# revA.net
KiCad netlist of a schematic drawn in EAGLE
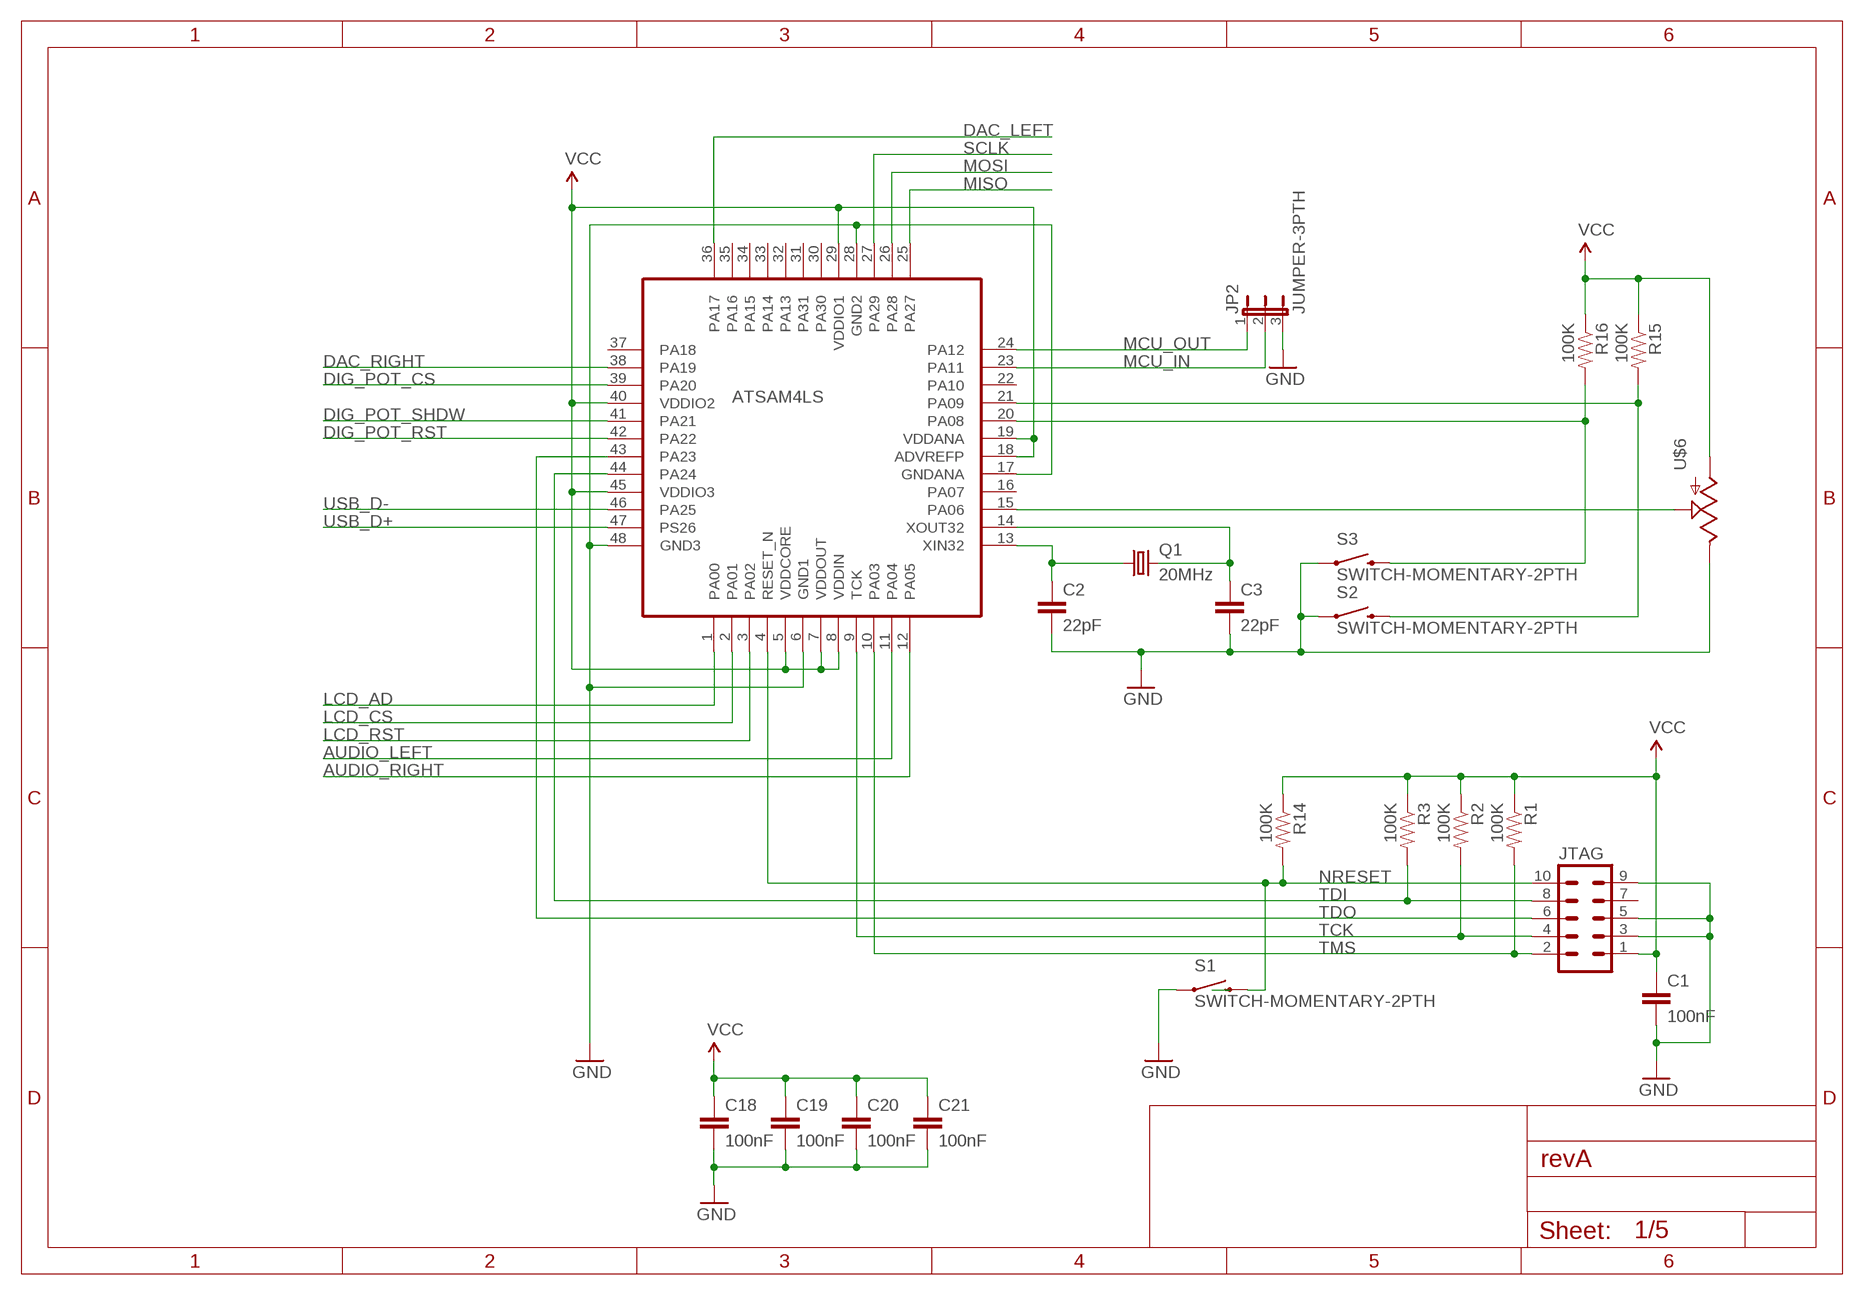
[diagram p0: schematic, sheet 1]
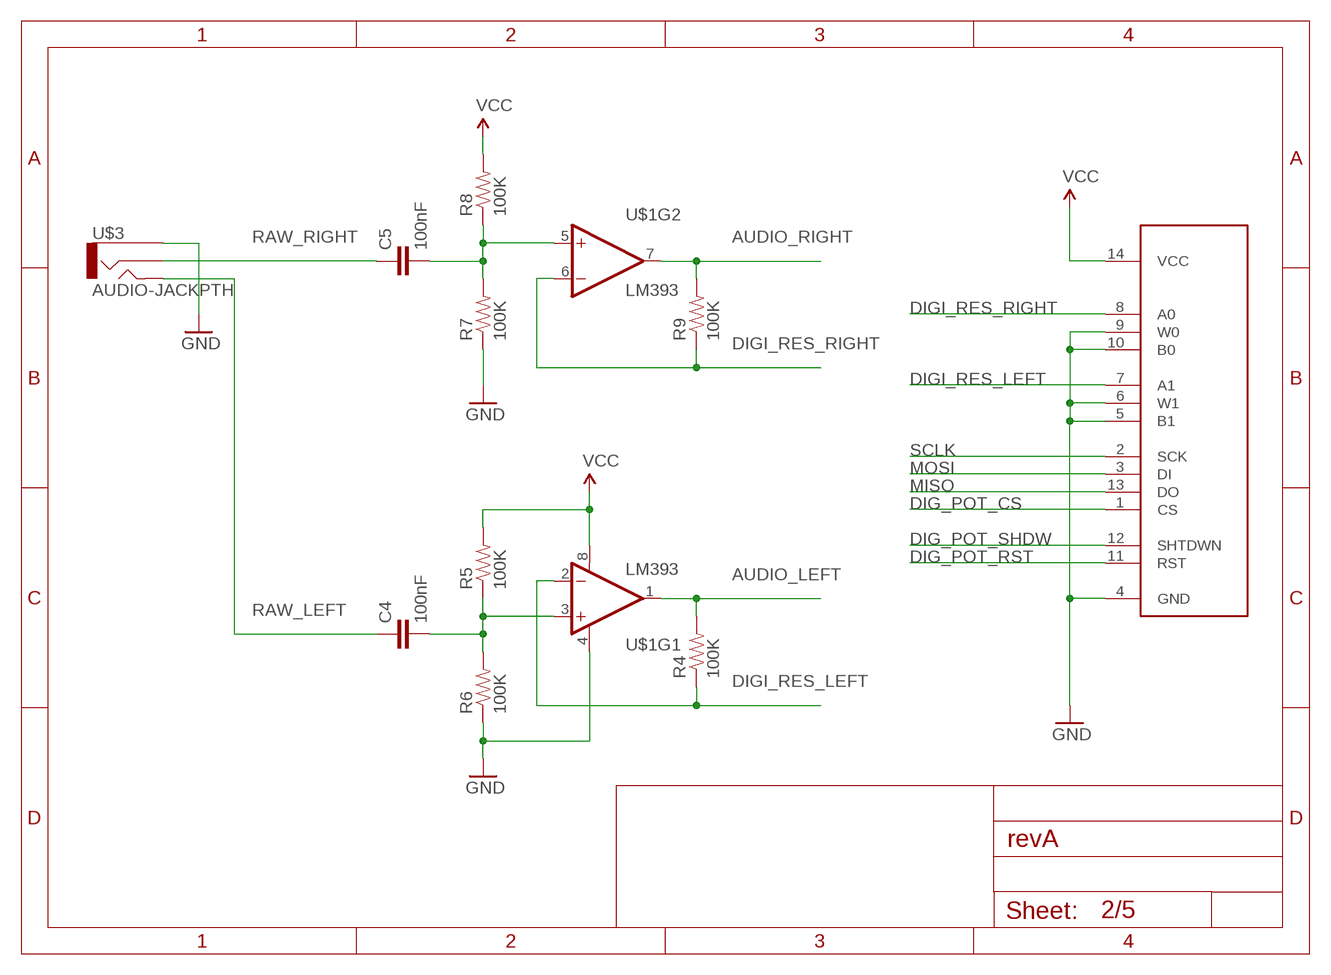
[diagram p1: schematic, sheet 2]
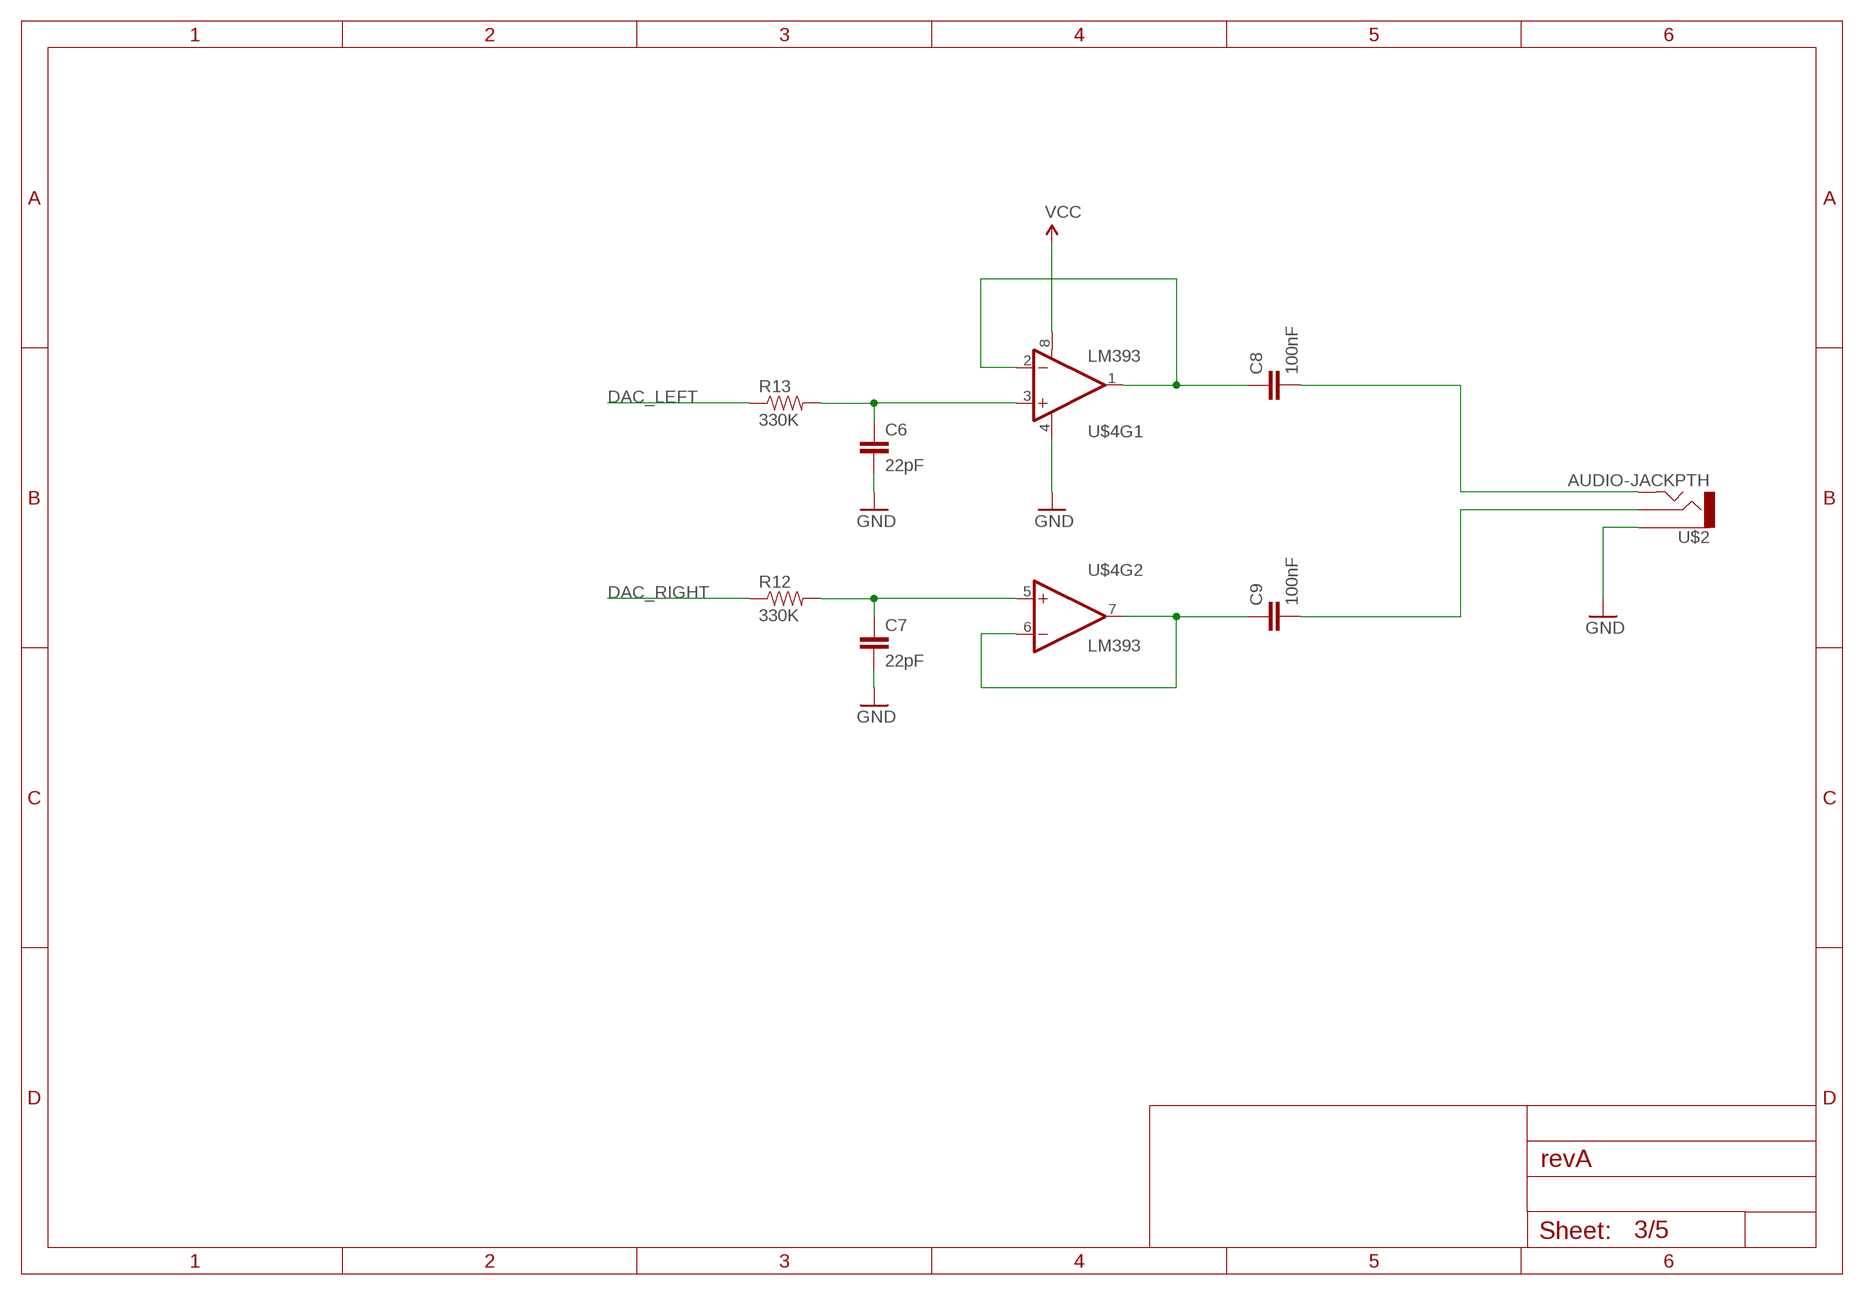
[diagram p2: schematic, sheet 3]
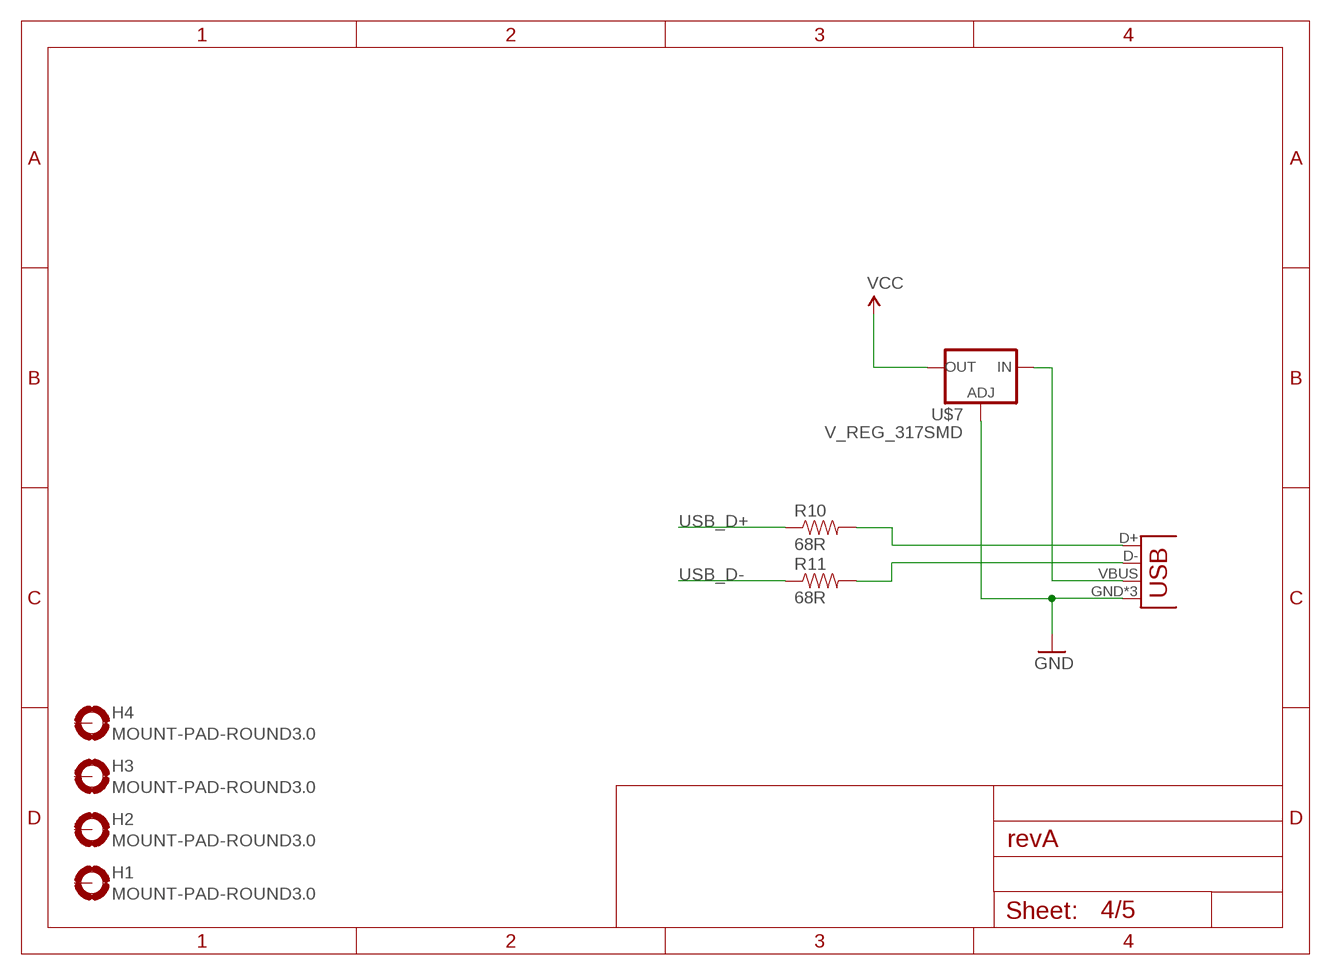
[diagram p3: schematic, sheet 4]
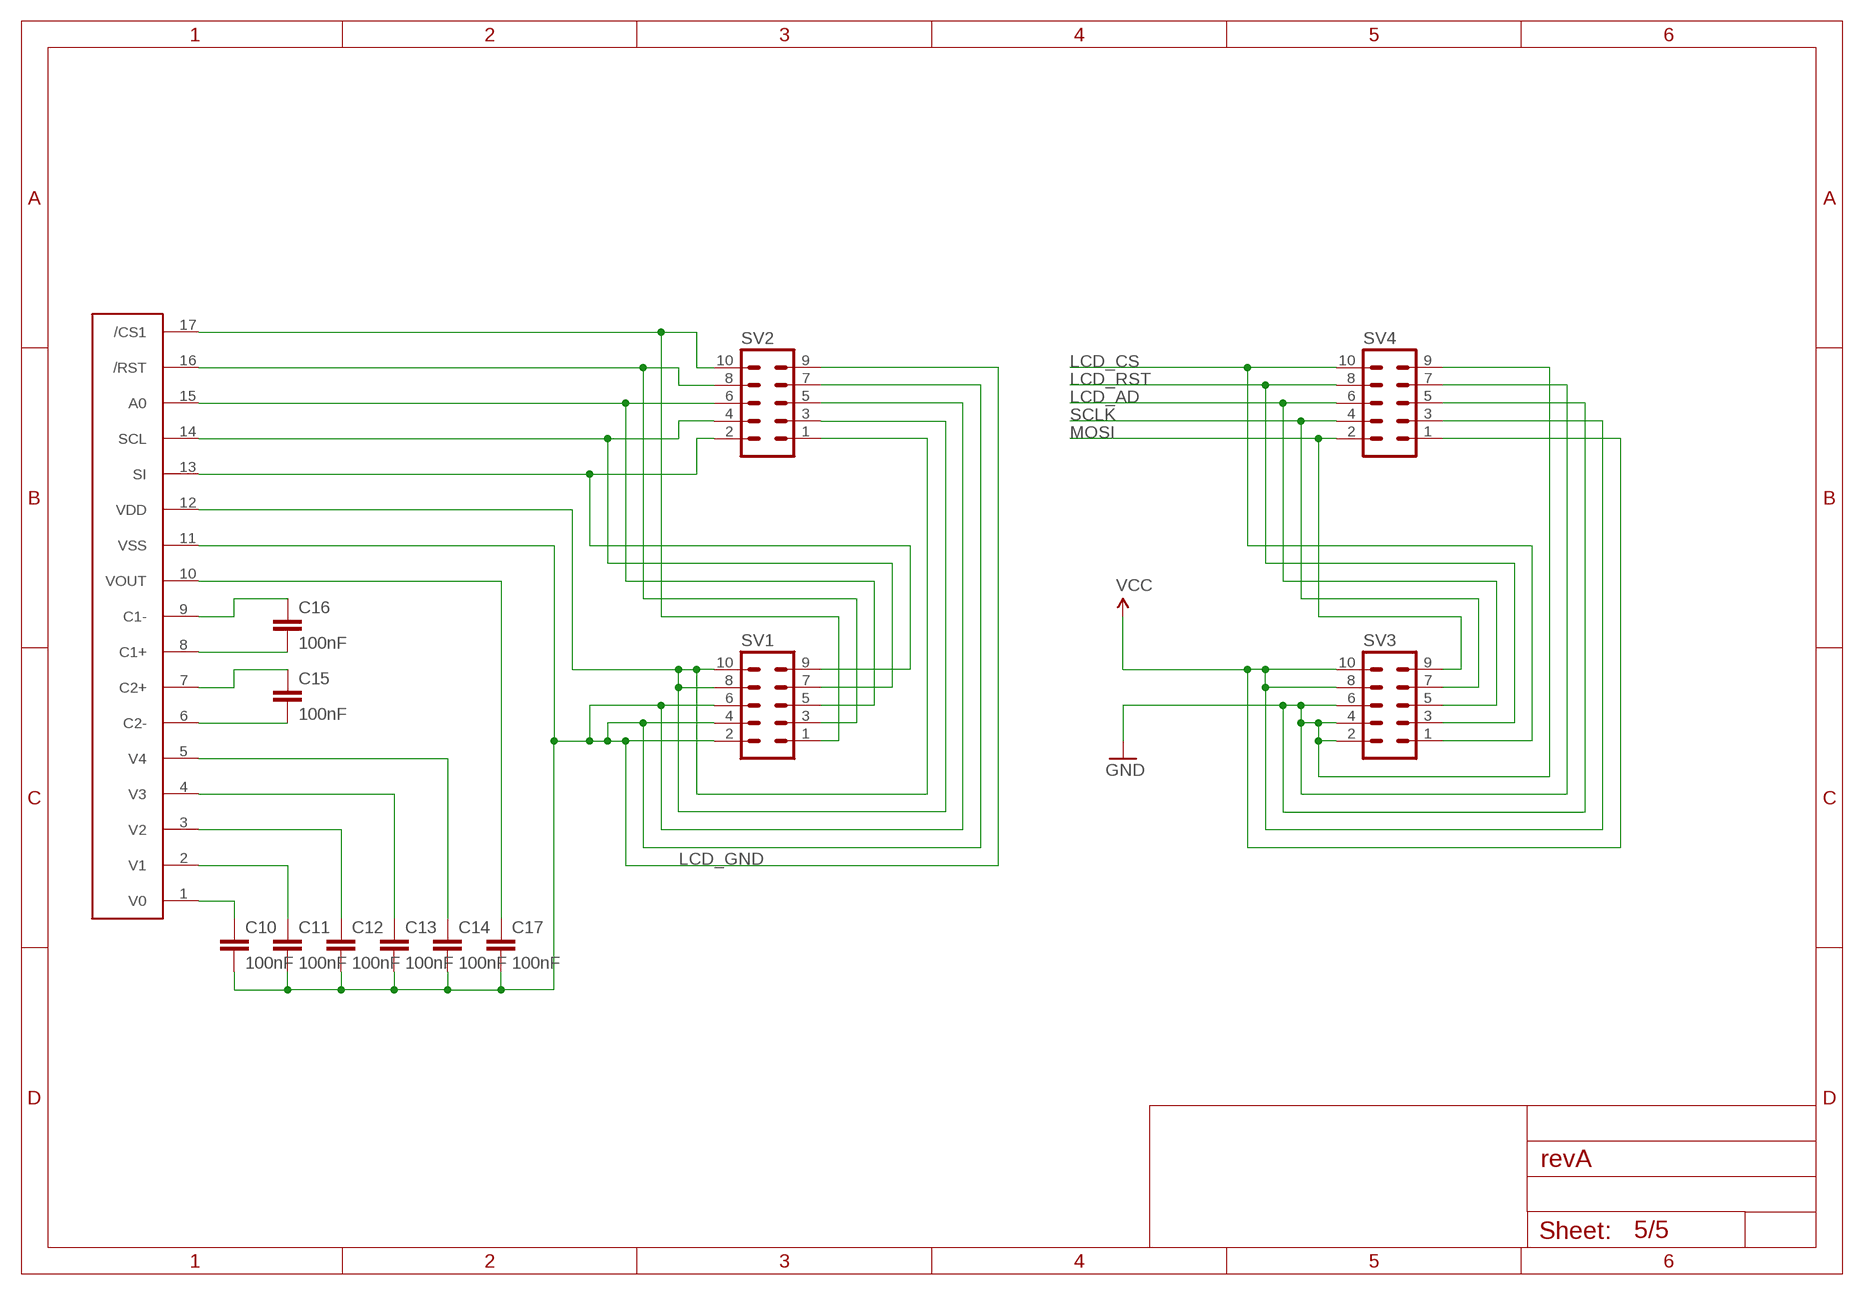
[diagram p4: schematic, sheet 5]

(export (version "E")
  (design (tool "Eeschema 10.0.6"))
  (components
    (comp (ref "ATSAM4LS")
      (value "ATSAM4LSAA-AUR")
      (footprint "eagle-import:TQFP48")
      (libsource (lib "eagle-import") (part "ATSAM4LSAA-AUR"))
    )
    (comp (ref "C1")
      (value "100nF")
      (footprint "eagle-import:0805")
      (libsource (lib "eagle-import") (part "CAP0805"))
    )
    (comp (ref "C2")
      (value "22pF")
      (footprint "eagle-import:0805")
      (libsource (lib "eagle-import") (part "CAP0805"))
    )
    (comp (ref "C3")
      (value "22pF")
      (footprint "eagle-import:0805")
      (libsource (lib "eagle-import") (part "CAP0805"))
    )
    (comp (ref "C18")
      (value "100nF")
      (footprint "eagle-import:0805")
      (libsource (lib "eagle-import") (part "CAP0805"))
    )
    (comp (ref "C19")
      (value "100nF")
      (footprint "eagle-import:0805")
      (libsource (lib "eagle-import") (part "CAP0805"))
    )
    (comp (ref "C20")
      (value "100nF")
      (footprint "eagle-import:0805")
      (libsource (lib "eagle-import") (part "CAP0805"))
    )
    (comp (ref "C21")
      (value "100nF")
      (footprint "eagle-import:0805")
      (libsource (lib "eagle-import") (part "CAP0805"))
    )
    (comp (ref "JP2")
      (value "JUMPER-3PTH")
      (footprint "eagle-import:1X03")
      (libsource (lib "eagle-import") (part "JUMPER-3PTH"))
    )
    (comp (ref "JTAG")
      (value "MA05-2")
      (footprint "eagle-import:MA05-2")
      (libsource (lib "eagle-import") (part "MA05-2"))
    )
    (comp (ref "Q1")
      (value "20MHz")
      (footprint "eagle-import:HC49U-V")
      (libsource (lib "eagle-import") (part "CRYSTALHC49UV"))
    )
    (comp (ref "R1")
      (value "100K")
      (footprint "eagle-import:1206")
      (libsource (lib "eagle-import") (part "RESISTOR1206"))
    )
    (comp (ref "R2")
      (value "100K")
      (footprint "eagle-import:1206")
      (libsource (lib "eagle-import") (part "RESISTOR1206"))
    )
    (comp (ref "R3")
      (value "100K")
      (footprint "eagle-import:1206")
      (libsource (lib "eagle-import") (part "RESISTOR1206"))
    )
    (comp (ref "R14")
      (value "100K")
      (footprint "eagle-import:1206")
      (libsource (lib "eagle-import") (part "RESISTOR1206"))
    )
    (comp (ref "R15")
      (value "100K")
      (footprint "eagle-import:1206")
      (libsource (lib "eagle-import") (part "RESISTOR1206"))
    )
    (comp (ref "R16")
      (value "100K")
      (footprint "eagle-import:1206")
      (libsource (lib "eagle-import") (part "RESISTOR1206"))
    )
    (comp (ref "S1")
      (value "SWITCH-MOMENTARY-2PTH")
      (footprint "eagle-import:TACTILE-PTH")
      (libsource (lib "eagle-import") (part "SWITCH-MOMENTARY-2PTH"))
    )
    (comp (ref "S2")
      (value "SWITCH-MOMENTARY-2PTH")
      (footprint "eagle-import:TACTILE-PTH")
      (libsource (lib "eagle-import") (part "SWITCH-MOMENTARY-2PTH"))
    )
    (comp (ref "S3")
      (value "SWITCH-MOMENTARY-2PTH")
      (footprint "eagle-import:TACTILE-PTH")
      (libsource (lib "eagle-import") (part "SWITCH-MOMENTARY-2PTH"))
    )
    (comp (ref "U$6")
      (value "POTTRIM")
      (footprint "eagle-import:TRIM_POT")
      (libsource (lib "eagle-import") (part "POTTRIM"))
    )
    (comp (ref "C4")
      (value "100nF")
      (footprint "eagle-import:0805")
      (libsource (lib "eagle-import") (part "CAP0805"))
    )
    (comp (ref "C5")
      (value "100nF")
      (footprint "eagle-import:0805")
      (libsource (lib "eagle-import") (part "CAP0805"))
    )
    (comp (ref "R4")
      (value "100K")
      (footprint "eagle-import:1206")
      (libsource (lib "eagle-import") (part "RESISTOR1206"))
    )
    (comp (ref "R5")
      (value "100K")
      (footprint "eagle-import:1206")
      (libsource (lib "eagle-import") (part "RESISTOR1206"))
    )
    (comp (ref "R6")
      (value "100K")
      (footprint "eagle-import:1206")
      (libsource (lib "eagle-import") (part "RESISTOR1206"))
    )
    (comp (ref "R7")
      (value "100K")
      (footprint "eagle-import:1206")
      (libsource (lib "eagle-import") (part "RESISTOR1206"))
    )
    (comp (ref "R8")
      (value "100K")
      (footprint "eagle-import:1206")
      (libsource (lib "eagle-import") (part "RESISTOR1206"))
    )
    (comp (ref "R9")
      (value "100K")
      (footprint "eagle-import:1206")
      (libsource (lib "eagle-import") (part "RESISTOR1206"))
    )
    (comp (ref "U$1")
      (value "LM393")
      (footprint "eagle-import:SO08")
      (libsource (lib "eagle-import") (part "LM393"))
    )
    (comp (ref "U$3")
      (value "AUDIO-JACKPTH")
      (footprint "eagle-import:AUDIO-JACK")
      (libsource (lib "eagle-import") (part "AUDIO-JACKPTH"))
    )
    (comp (ref "U1")
      (value "MCP42XXX")
      (footprint "eagle-import:SO014")
      (libsource (lib "eagle-import") (part "MCP42XXX"))
    )
    (comp (ref "C6")
      (value "22pF")
      (footprint "eagle-import:0805")
      (libsource (lib "eagle-import") (part "CAP0805"))
    )
    (comp (ref "C7")
      (value "22pF")
      (footprint "eagle-import:0805")
      (libsource (lib "eagle-import") (part "CAP0805"))
    )
    (comp (ref "C8")
      (value "100nF")
      (footprint "eagle-import:0805")
      (libsource (lib "eagle-import") (part "CAP0805"))
    )
    (comp (ref "C9")
      (value "100nF")
      (footprint "eagle-import:0805")
      (libsource (lib "eagle-import") (part "CAP0805"))
    )
    (comp (ref "R12")
      (value "330K")
      (footprint "eagle-import:1206")
      (libsource (lib "eagle-import") (part "RESISTOR1206"))
    )
    (comp (ref "R13")
      (value "330K")
      (footprint "eagle-import:1206")
      (libsource (lib "eagle-import") (part "RESISTOR1206"))
    )
    (comp (ref "U$2")
      (value "AUDIO-JACKPTH")
      (footprint "eagle-import:AUDIO-JACK")
      (libsource (lib "eagle-import") (part "AUDIO-JACKPTH"))
    )
    (comp (ref "U$4")
      (value "LM393")
      (footprint "eagle-import:SO08")
      (libsource (lib "eagle-import") (part "LM393"))
    )
    (comp (ref "C10")
      (value "100nF")
      (footprint "eagle-import:0805")
      (libsource (lib "eagle-import") (part "CAP0805"))
    )
    (comp (ref "C11")
      (value "100nF")
      (footprint "eagle-import:0805")
      (libsource (lib "eagle-import") (part "CAP0805"))
    )
    (comp (ref "C12")
      (value "100nF")
      (footprint "eagle-import:0805")
      (libsource (lib "eagle-import") (part "CAP0805"))
    )
    (comp (ref "C13")
      (value "100nF")
      (footprint "eagle-import:0805")
      (libsource (lib "eagle-import") (part "CAP0805"))
    )
    (comp (ref "C14")
      (value "100nF")
      (footprint "eagle-import:0805")
      (libsource (lib "eagle-import") (part "CAP0805"))
    )
    (comp (ref "C15")
      (value "100nF")
      (footprint "eagle-import:0805")
      (libsource (lib "eagle-import") (part "CAP0805"))
    )
    (comp (ref "C16")
      (value "100nF")
      (footprint "eagle-import:0805")
      (libsource (lib "eagle-import") (part "CAP0805"))
    )
    (comp (ref "C17")
      (value "100nF")
      (footprint "eagle-import:0805")
      (libsource (lib "eagle-import") (part "CAP0805"))
    )
    (comp (ref "SV1")
      (value "MA05-2")
      (footprint "eagle-import:MA05-2")
      (libsource (lib "eagle-import") (part "MA05-2"))
    )
    (comp (ref "SV2")
      (value "MA05-2")
      (footprint "eagle-import:MA05-2")
      (libsource (lib "eagle-import") (part "MA05-2"))
    )
    (comp (ref "SV3")
      (value "MA05-2")
      (footprint "eagle-import:MA05-2")
      (fields (field (name "OC_FARNELL") "unknown") (field (name "OC_NEWARK") "unknown"))
      (libsource (lib "eagle-import") (part "MA05-2"))
    )
    (comp (ref "SV4")
      (value "MA05-2")
      (footprint "eagle-import:MA05-2")
      (fields (field (name "OC_FARNELL") "unknown") (field (name "OC_NEWARK") "unknown"))
      (libsource (lib "eagle-import") (part "MA05-2"))
    )
    (comp (ref "U$5")
      (value "NHD_128X32")
      (footprint "eagle-import:NHD_128X32")
      (libsource (lib "eagle-import") (part "NHD_128X32"))
    )
    (comp (ref "H1")
      (value "MOUNT-PAD-ROUND3.0")
      (footprint "eagle-import:3,0-PAD")
      (libsource (lib "eagle-import") (part "MOUNT-PAD-ROUND3.0"))
    )
    (comp (ref "H2")
      (value "MOUNT-PAD-ROUND3.0")
      (footprint "eagle-import:3,0-PAD")
      (libsource (lib "eagle-import") (part "MOUNT-PAD-ROUND3.0"))
    )
    (comp (ref "H3")
      (value "MOUNT-PAD-ROUND3.0")
      (footprint "eagle-import:3,0-PAD")
      (libsource (lib "eagle-import") (part "MOUNT-PAD-ROUND3.0"))
    )
    (comp (ref "H4")
      (value "MOUNT-PAD-ROUND3.0")
      (footprint "eagle-import:3,0-PAD")
      (libsource (lib "eagle-import") (part "MOUNT-PAD-ROUND3.0"))
    )
    (comp (ref "JP1")
      (value "USB-MICROB")
      (footprint "eagle-import:USB-MICROB")
      (libsource (lib "eagle-import") (part "USB-MICROB"))
    )
    (comp (ref "R10")
      (value "68R")
      (footprint "eagle-import:1206")
      (libsource (lib "eagle-import") (part "RESISTOR1206"))
    )
    (comp (ref "R11")
      (value "68R")
      (footprint "eagle-import:1206")
      (libsource (lib "eagle-import") (part "RESISTOR1206"))
    )
    (comp (ref "U$7")
      (value "V_REG_317SMD")
      (footprint "eagle-import:SOT223")
      (libsource (lib "eagle-import") (part "V_REG_317SMD"))
    )
  )
  (nets
    (net (code "1") (name "AUDIO_LEFT") (class "Default")
      (node (ref "ATSAM4LS") (pin "11") (pinfunction "PA04_11") (pintype "bidirectional"))
      (node (ref "R4") (pin "2") (pinfunction "2_2") (pintype "passive"))
      (node (ref "U$1") (pin "1") (pinfunction "OUT_1") (pintype "output"))
    )
    (net (code "2") (name "AUDIO_RIGHT") (class "Default")
      (node (ref "ATSAM4LS") (pin "12") (pinfunction "PA05_12") (pintype "bidirectional"))
      (node (ref "R9") (pin "2") (pinfunction "2_2") (pintype "passive"))
      (node (ref "U$1") (pin "7") (pinfunction "OUT_7") (pintype "output"))
    )
    (net (code "3") (name "DAC_LEFT") (class "Default")
      (node (ref "ATSAM4LS") (pin "36") (pinfunction "PA17_36") (pintype "bidirectional"))
      (node (ref "R13") (pin "1") (pinfunction "1_1") (pintype "passive"))
    )
    (net (code "4") (name "DAC_RIGHT") (class "Default")
      (node (ref "ATSAM4LS") (pin "38") (pinfunction "PA19_38") (pintype "bidirectional"))
      (node (ref "R12") (pin "1") (pinfunction "1_1") (pintype "passive"))
    )
    (net (code "5") (name "DIGI_RES_LEFT") (class "Default")
      (node (ref "R4") (pin "1") (pinfunction "1_1") (pintype "passive"))
      (node (ref "U$1") (pin "2") (pinfunction "-IN_2") (pintype "input"))
      (node (ref "U1") (pin "7") (pinfunction "A1_7") (pintype "bidirectional"))
    )
    (net (code "6") (name "DIGI_RES_RIGHT") (class "Default")
      (node (ref "R9") (pin "1") (pinfunction "1_1") (pintype "passive"))
      (node (ref "U$1") (pin "6") (pinfunction "-IN_6") (pintype "input"))
      (node (ref "U1") (pin "8") (pinfunction "A0_8") (pintype "bidirectional"))
    )
    (net (code "7") (name "DIG_POT_CS") (class "Default")
      (node (ref "ATSAM4LS") (pin "39") (pinfunction "PA20_39") (pintype "bidirectional"))
      (node (ref "U1") (pin "1") (pinfunction "CS_1") (pintype "bidirectional"))
    )
    (net (code "8") (name "DIG_POT_RST") (class "Default")
      (node (ref "ATSAM4LS") (pin "42") (pinfunction "PA22_42") (pintype "bidirectional"))
      (node (ref "U1") (pin "11") (pinfunction "RST_11") (pintype "bidirectional"))
    )
    (net (code "9") (name "DIG_POT_SHDW") (class "Default")
      (node (ref "ATSAM4LS") (pin "41") (pinfunction "PA21_41") (pintype "bidirectional"))
      (node (ref "U1") (pin "12") (pinfunction "SHTDWN_12") (pintype "bidirectional"))
    )
    (net (code "10") (name "GND") (class "Default")
      (node (ref "ATSAM4LS") (pin "17") (pinfunction "GNDANA_17") (pintype "bidirectional"))
      (node (ref "ATSAM4LS") (pin "28") (pinfunction "GND2_28") (pintype "bidirectional"))
      (node (ref "ATSAM4LS") (pin "48") (pinfunction "GND3_48") (pintype "bidirectional"))
      (node (ref "ATSAM4LS") (pin "6") (pinfunction "GND1_6") (pintype "bidirectional"))
      (node (ref "C1") (pin "2") (pinfunction "2_2") (pintype "passive"))
      (node (ref "C18") (pin "2") (pinfunction "2_2") (pintype "passive"))
      (node (ref "C19") (pin "2") (pinfunction "2_2") (pintype "passive"))
      (node (ref "C2") (pin "2") (pinfunction "2_2") (pintype "passive"))
      (node (ref "C20") (pin "2") (pinfunction "2_2") (pintype "passive"))
      (node (ref "C21") (pin "2") (pinfunction "2_2") (pintype "passive"))
      (node (ref "C3") (pin "2") (pinfunction "2_2") (pintype "passive"))
      (node (ref "C6") (pin "2") (pinfunction "2_2") (pintype "passive"))
      (node (ref "C7") (pin "2") (pinfunction "2_2") (pintype "passive"))
      (node (ref "JP1") (pin "GND") (pinfunction "GND_GND") (pintype "bidirectional"))
      (node (ref "JP1") (pin "MT1") (pinfunction "GND_MT1") (pintype "bidirectional"))
      (node (ref "JP1") (pin "MT2") (pinfunction "GND_MT2") (pintype "bidirectional"))
      (node (ref "JP2") (pin "3") (pinfunction "3_3") (pintype "passive"))
      (node (ref "JTAG") (pin "3") (pinfunction "3_3") (pintype "passive"))
      (node (ref "JTAG") (pin "5") (pinfunction "5_5") (pintype "passive"))
      (node (ref "JTAG") (pin "9") (pinfunction "9_9") (pintype "passive"))
      (node (ref "R6") (pin "1") (pinfunction "1_1") (pintype "passive"))
      (node (ref "R7") (pin "1") (pinfunction "1_1") (pintype "passive"))
      (node (ref "S1") (pin "1") (pinfunction "1_1") (pintype "passive"))
      (node (ref "S2") (pin "1") (pinfunction "1_1") (pintype "passive"))
      (node (ref "S3") (pin "1") (pinfunction "1_1") (pintype "passive"))
      (node (ref "SV3") (pin "2") (pinfunction "2_2") (pintype "passive"))
      (node (ref "SV3") (pin "4") (pinfunction "4_4") (pintype "passive"))
      (node (ref "SV3") (pin "6") (pinfunction "6_6") (pintype "passive"))
      (node (ref "SV4") (pin "5") (pinfunction "5_5") (pintype "passive"))
      (node (ref "SV4") (pin "7") (pinfunction "7_7") (pintype "passive"))
      (node (ref "SV4") (pin "9") (pinfunction "9_9") (pintype "passive"))
      (node (ref "U$1") (pin "4") (pinfunction "V-_4") (pintype "power_in"))
      (node (ref "U$2") (pin "1") (pinfunction "1_1") (pintype "bidirectional"))
      (node (ref "U$3") (pin "1") (pinfunction "1_1") (pintype "bidirectional"))
      (node (ref "U$4") (pin "4") (pinfunction "V-_4") (pintype "power_in"))
      (node (ref "U$6") (pin "2") (pinfunction "E_2") (pintype "passive"))
      (node (ref "U$7") (pin "1") (pinfunction "ADJ_1") (pintype "input"))
      (node (ref "U1") (pin "10") (pinfunction "B0_10") (pintype "bidirectional"))
      (node (ref "U1") (pin "4") (pinfunction "GND_4") (pintype "bidirectional"))
      (node (ref "U1") (pin "5") (pinfunction "B1_5") (pintype "bidirectional"))
      (node (ref "U1") (pin "6") (pinfunction "W1_6") (pintype "bidirectional"))
      (node (ref "U1") (pin "9") (pinfunction "W0_9") (pintype "bidirectional"))
    )
    (net (code "11") (name "LCD_AD") (class "Default")
      (node (ref "ATSAM4LS") (pin "1") (pinfunction "PA00_1") (pintype "bidirectional"))
      (node (ref "SV3") (pin "5") (pinfunction "5_5") (pintype "passive"))
      (node (ref "SV4") (pin "6") (pinfunction "6_6") (pintype "passive"))
    )
    (net (code "12") (name "LCD_CS") (class "Default")
      (node (ref "ATSAM4LS") (pin "2") (pinfunction "PA01_2") (pintype "bidirectional"))
      (node (ref "SV3") (pin "1") (pinfunction "1_1") (pintype "passive"))
      (node (ref "SV4") (pin "10") (pinfunction "10_10") (pintype "passive"))
    )
    (net (code "13") (name "LCD_GND") (class "Default")
      (node (ref "C10") (pin "2") (pinfunction "2_2") (pintype "passive"))
      (node (ref "C11") (pin "2") (pinfunction "2_2") (pintype "passive"))
      (node (ref "C12") (pin "2") (pinfunction "2_2") (pintype "passive"))
      (node (ref "C13") (pin "2") (pinfunction "2_2") (pintype "passive"))
      (node (ref "C14") (pin "2") (pinfunction "2_2") (pintype "passive"))
      (node (ref "C17") (pin "2") (pinfunction "2_2") (pintype "passive"))
      (node (ref "SV1") (pin "2") (pinfunction "2_2") (pintype "passive"))
      (node (ref "SV1") (pin "4") (pinfunction "4_4") (pintype "passive"))
      (node (ref "SV1") (pin "6") (pinfunction "6_6") (pintype "passive"))
      (node (ref "SV2") (pin "5") (pinfunction "5_5") (pintype "passive"))
      (node (ref "SV2") (pin "7") (pinfunction "7_7") (pintype "passive"))
      (node (ref "SV2") (pin "9") (pinfunction "9_9") (pintype "passive"))
      (node (ref "U$5") (pin "11") (pinfunction "VSS_11") (pintype "bidirectional"))
    )
    (net (code "14") (name "LCD_RST") (class "Default")
      (node (ref "ATSAM4LS") (pin "3") (pinfunction "PA02_3") (pintype "bidirectional"))
      (node (ref "SV3") (pin "3") (pinfunction "3_3") (pintype "passive"))
      (node (ref "SV4") (pin "8") (pinfunction "8_8") (pintype "passive"))
    )
    (net (code "15") (name "MCU_IN") (class "Default")
      (node (ref "ATSAM4LS") (pin "23") (pinfunction "PA11_23") (pintype "bidirectional"))
      (node (ref "JP2") (pin "2") (pinfunction "2_2") (pintype "passive"))
    )
    (net (code "16") (name "MCU_OUT") (class "Default")
      (node (ref "ATSAM4LS") (pin "24") (pinfunction "PA12_24") (pintype "bidirectional"))
      (node (ref "JP2") (pin "1") (pinfunction "1_1") (pintype "passive"))
    )
    (net (code "17") (name "MISO") (class "Default")
      (node (ref "ATSAM4LS") (pin "25") (pinfunction "PA27_25") (pintype "bidirectional"))
      (node (ref "U1") (pin "13") (pinfunction "DO_13") (pintype "bidirectional"))
    )
    (net (code "18") (name "MOSI") (class "Default")
      (node (ref "ATSAM4LS") (pin "26") (pinfunction "PA28_26") (pintype "bidirectional"))
      (node (ref "SV3") (pin "9") (pinfunction "9_9") (pintype "passive"))
      (node (ref "SV4") (pin "2") (pinfunction "2_2") (pintype "passive"))
      (node (ref "U1") (pin "3") (pinfunction "DI_3") (pintype "bidirectional"))
    )
    (net (code "19") (name "NRESET") (class "Default")
      (node (ref "ATSAM4LS") (pin "4") (pinfunction "RESET_N_4") (pintype "bidirectional"))
      (node (ref "JTAG") (pin "10") (pinfunction "10_10") (pintype "passive"))
      (node (ref "R14") (pin "2") (pinfunction "2_2") (pintype "passive"))
      (node (ref "S1") (pin "3") (pinfunction "2_3") (pintype "passive"))
    )
    (net (code "20") (name "Net-(ATSAM4LS-PA06)") (class "Default")
      (node (ref "ATSAM4LS") (pin "15") (pinfunction "PA06_15") (pintype "bidirectional"))
      (node (ref "U$6") (pin "1") (pinfunction "S_1") (pintype "passive"))
    )
    (net (code "21") (name "Net-(ATSAM4LS-PA08)") (class "Default")
      (node (ref "ATSAM4LS") (pin "20") (pinfunction "PA08_20") (pintype "bidirectional"))
      (node (ref "R16") (pin "2") (pinfunction "2_2") (pintype "passive"))
      (node (ref "S3") (pin "3") (pinfunction "2_3") (pintype "passive"))
    )
    (net (code "22") (name "Net-(ATSAM4LS-PA09)") (class "Default")
      (node (ref "ATSAM4LS") (pin "21") (pinfunction "PA09_21") (pintype "bidirectional"))
      (node (ref "R15") (pin "2") (pinfunction "2_2") (pintype "passive"))
      (node (ref "S2") (pin "3") (pinfunction "2_3") (pintype "passive"))
    )
    (net (code "23") (name "Net-(ATSAM4LS-XIN32)") (class "Default")
      (node (ref "ATSAM4LS") (pin "13") (pinfunction "XIN32_13") (pintype "bidirectional"))
      (node (ref "C2") (pin "1") (pinfunction "1_1") (pintype "passive"))
      (node (ref "Q1") (pin "1") (pinfunction "1_1") (pintype "passive"))
    )
    (net (code "24") (name "Net-(ATSAM4LS-XOUT32)") (class "Default")
      (node (ref "ATSAM4LS") (pin "14") (pinfunction "XOUT32_14") (pintype "bidirectional"))
      (node (ref "C3") (pin "1") (pinfunction "1_1") (pintype "passive"))
      (node (ref "Q1") (pin "2") (pinfunction "2_2") (pintype "passive"))
    )
    (net (code "25") (name "Net-(C8-Pad2)") (class "Default")
      (node (ref "C8") (pin "2") (pinfunction "2_2") (pintype "passive"))
      (node (ref "U$2") (pin "5") (pinfunction "5_5") (pintype "bidirectional"))
    )
    (net (code "26") (name "Net-(C9-Pad2)") (class "Default")
      (node (ref "C9") (pin "2") (pinfunction "2_2") (pintype "passive"))
      (node (ref "U$2") (pin "2") (pinfunction "2_2") (pintype "bidirectional"))
    )
    (net (code "27") (name "Net-(JP1-PadD+)") (class "Default")
      (node (ref "JP1") (pin "D+") (pinfunction "D+_D+") (pintype "bidirectional"))
      (node (ref "R10") (pin "2") (pinfunction "2_2") (pintype "passive"))
    )
    (net (code "28") (name "Net-(JP1-PadD-)") (class "Default")
      (node (ref "JP1") (pin "D-") (pinfunction "D-_D-") (pintype "bidirectional"))
      (node (ref "R11") (pin "2") (pinfunction "2_2") (pintype "passive"))
    )
    (net (code "29") (name "Net-(U$1A-+IN)") (class "Default")
      (node (ref "C4") (pin "2") (pinfunction "2_2") (pintype "passive"))
      (node (ref "R5") (pin "1") (pinfunction "1_1") (pintype "passive"))
      (node (ref "R6") (pin "2") (pinfunction "2_2") (pintype "passive"))
      (node (ref "U$1") (pin "3") (pinfunction "+IN_3") (pintype "input"))
    )
    (net (code "30") (name "Net-(U$1B-+IN)") (class "Default")
      (node (ref "C5") (pin "2") (pinfunction "2_2") (pintype "passive"))
      (node (ref "R7") (pin "2") (pinfunction "2_2") (pintype "passive"))
      (node (ref "R8") (pin "1") (pinfunction "1_1") (pintype "passive"))
      (node (ref "U$1") (pin "5") (pinfunction "+IN_5") (pintype "input"))
    )
    (net (code "31") (name "Net-(U$4A-+IN)") (class "Default")
      (node (ref "C6") (pin "1") (pinfunction "1_1") (pintype "passive"))
      (node (ref "R13") (pin "2") (pinfunction "2_2") (pintype "passive"))
      (node (ref "U$4") (pin "3") (pinfunction "+IN_3") (pintype "input"))
    )
    (net (code "32") (name "Net-(U$4A--IN)") (class "Default")
      (node (ref "C8") (pin "1") (pinfunction "1_1") (pintype "passive"))
      (node (ref "U$4") (pin "1") (pinfunction "OUT_1") (pintype "output"))
      (node (ref "U$4") (pin "2") (pinfunction "-IN_2") (pintype "input"))
    )
    (net (code "33") (name "Net-(U$4B-+IN)") (class "Default")
      (node (ref "C7") (pin "1") (pinfunction "1_1") (pintype "passive"))
      (node (ref "R12") (pin "2") (pinfunction "2_2") (pintype "passive"))
      (node (ref "U$4") (pin "5") (pinfunction "+IN_5") (pintype "input"))
    )
    (net (code "34") (name "Net-(U$4B--IN)") (class "Default")
      (node (ref "C9") (pin "1") (pinfunction "1_1") (pintype "passive"))
      (node (ref "U$4") (pin "6") (pinfunction "-IN_6") (pintype "input"))
      (node (ref "U$4") (pin "7") (pinfunction "OUT_7") (pintype "output"))
    )
    (net (code "35") (name "Net-(U$5-A0)") (class "Default")
      (node (ref "SV1") (pin "5") (pinfunction "5_5") (pintype "passive"))
      (node (ref "SV2") (pin "6") (pinfunction "6_6") (pintype "passive"))
      (node (ref "U$5") (pin "15") (pinfunction "A0_15") (pintype "bidirectional"))
    )
    (net (code "36") (name "Net-(U$5-C1+)") (class "Default")
      (node (ref "C16") (pin "2") (pinfunction "2_2") (pintype "passive"))
      (node (ref "U$5") (pin "8") (pinfunction "C1+_8") (pintype "bidirectional"))
    )
    (net (code "37") (name "Net-(U$5-C1-)") (class "Default")
      (node (ref "C16") (pin "1") (pinfunction "1_1") (pintype "passive"))
      (node (ref "U$5") (pin "9") (pinfunction "C1-_9") (pintype "bidirectional"))
    )
    (net (code "38") (name "Net-(U$5-C2+)") (class "Default")
      (node (ref "C15") (pin "1") (pinfunction "1_1") (pintype "passive"))
      (node (ref "U$5") (pin "7") (pinfunction "C2+_7") (pintype "bidirectional"))
    )
    (net (code "39") (name "Net-(U$5-C2-)") (class "Default")
      (node (ref "C15") (pin "2") (pinfunction "2_2") (pintype "passive"))
      (node (ref "U$5") (pin "6") (pinfunction "C2-_6") (pintype "bidirectional"))
    )
    (net (code "40") (name "Net-(U$5-SCL)") (class "Default")
      (node (ref "SV1") (pin "7") (pinfunction "7_7") (pintype "passive"))
      (node (ref "SV2") (pin "4") (pinfunction "4_4") (pintype "passive"))
      (node (ref "U$5") (pin "14") (pinfunction "SCL_14") (pintype "bidirectional"))
    )
    (net (code "41") (name "Net-(U$5-SI)") (class "Default")
      (node (ref "SV1") (pin "9") (pinfunction "9_9") (pintype "passive"))
      (node (ref "SV2") (pin "2") (pinfunction "2_2") (pintype "passive"))
      (node (ref "U$5") (pin "13") (pinfunction "SI_13") (pintype "bidirectional"))
    )
    (net (code "42") (name "Net-(U$5-V0)") (class "Default")
      (node (ref "C10") (pin "1") (pinfunction "1_1") (pintype "passive"))
      (node (ref "U$5") (pin "1") (pinfunction "V0_1") (pintype "bidirectional"))
    )
    (net (code "43") (name "Net-(U$5-V1)") (class "Default")
      (node (ref "C11") (pin "1") (pinfunction "1_1") (pintype "passive"))
      (node (ref "U$5") (pin "2") (pinfunction "V1_2") (pintype "bidirectional"))
    )
    (net (code "44") (name "Net-(U$5-V2)") (class "Default")
      (node (ref "C12") (pin "1") (pinfunction "1_1") (pintype "passive"))
      (node (ref "U$5") (pin "3") (pinfunction "V2_3") (pintype "bidirectional"))
    )
    (net (code "45") (name "Net-(U$5-V3)") (class "Default")
      (node (ref "C13") (pin "1") (pinfunction "1_1") (pintype "passive"))
      (node (ref "U$5") (pin "4") (pinfunction "V3_4") (pintype "bidirectional"))
    )
    (net (code "46") (name "Net-(U$5-V4)") (class "Default")
      (node (ref "C14") (pin "1") (pinfunction "1_1") (pintype "passive"))
      (node (ref "U$5") (pin "5") (pinfunction "V4_5") (pintype "bidirectional"))
    )
    (net (code "47") (name "Net-(U$5-VDD)") (class "Default")
      (node (ref "SV1") (pin "10") (pinfunction "10_10") (pintype "passive"))
      (node (ref "SV1") (pin "8") (pinfunction "8_8") (pintype "passive"))
      (node (ref "SV2") (pin "1") (pinfunction "1_1") (pintype "passive"))
      (node (ref "SV2") (pin "3") (pinfunction "3_3") (pintype "passive"))
      (node (ref "U$5") (pin "12") (pinfunction "VDD_12") (pintype "bidirectional"))
    )
    (net (code "48") (name "Net-(U$5-VOUT)") (class "Default")
      (node (ref "C17") (pin "1") (pinfunction "1_1") (pintype "passive"))
      (node (ref "U$5") (pin "10") (pinfunction "VOUT_10") (pintype "bidirectional"))
    )
    (net (code "49") (name "Net-(U$5-{slash}CS1)") (class "Default")
      (node (ref "SV1") (pin "1") (pinfunction "1_1") (pintype "passive"))
      (node (ref "SV2") (pin "10") (pinfunction "10_10") (pintype "passive"))
      (node (ref "U$5") (pin "17") (pinfunction "/CS1_17") (pintype "bidirectional"))
    )
    (net (code "50") (name "Net-(U$5-{slash}RST)") (class "Default")
      (node (ref "SV1") (pin "3") (pinfunction "3_3") (pintype "passive"))
      (node (ref "SV2") (pin "8") (pinfunction "8_8") (pintype "passive"))
      (node (ref "U$5") (pin "16") (pinfunction "/RST_16") (pintype "bidirectional"))
    )
    (net (code "51") (name "Net-(U$7-IN)") (class "Default")
      (node (ref "JP1") (pin "VBUS") (pinfunction "VBUS_VBUS") (pintype "bidirectional"))
      (node (ref "U$7") (pin "3") (pinfunction "IN_3") (pintype "input"))
    )
    (net (code "52") (name "RAW_LEFT") (class "Default")
      (node (ref "C4") (pin "1") (pinfunction "1_1") (pintype "passive"))
      (node (ref "U$3") (pin "5") (pinfunction "5_5") (pintype "bidirectional"))
    )
    (net (code "53") (name "RAW_RIGHT") (class "Default")
      (node (ref "C5") (pin "1") (pinfunction "1_1") (pintype "passive"))
      (node (ref "U$3") (pin "2") (pinfunction "2_2") (pintype "bidirectional"))
    )
    (net (code "54") (name "SCLK") (class "Default")
      (node (ref "ATSAM4LS") (pin "27") (pinfunction "PA29_27") (pintype "bidirectional"))
      (node (ref "SV3") (pin "7") (pinfunction "7_7") (pintype "passive"))
      (node (ref "SV4") (pin "4") (pinfunction "4_4") (pintype "passive"))
      (node (ref "U1") (pin "2") (pinfunction "SCK_2") (pintype "bidirectional"))
    )
    (net (code "55") (name "TCK") (class "Default")
      (node (ref "ATSAM4LS") (pin "9") (pinfunction "TCK_9") (pintype "bidirectional"))
      (node (ref "JTAG") (pin "4") (pinfunction "4_4") (pintype "passive"))
      (node (ref "R2") (pin "2") (pinfunction "2_2") (pintype "passive"))
    )
    (net (code "56") (name "TDI") (class "Default")
      (node (ref "ATSAM4LS") (pin "44") (pinfunction "PA24_44") (pintype "bidirectional"))
      (node (ref "JTAG") (pin "8") (pinfunction "8_8") (pintype "passive"))
      (node (ref "R3") (pin "2") (pinfunction "2_2") (pintype "passive"))
    )
    (net (code "57") (name "TDO") (class "Default")
      (node (ref "ATSAM4LS") (pin "43") (pinfunction "PA23_43") (pintype "bidirectional"))
      (node (ref "JTAG") (pin "6") (pinfunction "6_6") (pintype "passive"))
    )
    (net (code "58") (name "TMS") (class "Default")
      (node (ref "ATSAM4LS") (pin "10") (pinfunction "PA03_10") (pintype "bidirectional"))
      (node (ref "JTAG") (pin "2") (pinfunction "2_2") (pintype "passive"))
      (node (ref "R1") (pin "2") (pinfunction "2_2") (pintype "passive"))
    )
    (net (code "59") (name "USB_D+") (class "Default")
      (node (ref "ATSAM4LS") (pin "47") (pinfunction "PS26_47") (pintype "bidirectional"))
      (node (ref "R10") (pin "1") (pinfunction "1_1") (pintype "passive"))
    )
    (net (code "60") (name "USB_D-") (class "Default")
      (node (ref "ATSAM4LS") (pin "46") (pinfunction "PA25_46") (pintype "bidirectional"))
      (node (ref "R11") (pin "1") (pinfunction "1_1") (pintype "passive"))
    )
    (net (code "61") (name "VCC") (class "Default")
      (node (ref "ATSAM4LS") (pin "18") (pinfunction "ADVREFP_18") (pintype "bidirectional"))
      (node (ref "ATSAM4LS") (pin "19") (pinfunction "VDDANA_19") (pintype "bidirectional"))
      (node (ref "ATSAM4LS") (pin "29") (pinfunction "VDDIO1_29") (pintype "bidirectional"))
      (node (ref "ATSAM4LS") (pin "40") (pinfunction "VDDIO2_40") (pintype "bidirectional"))
      (node (ref "ATSAM4LS") (pin "45") (pinfunction "VDDIO3_45") (pintype "bidirectional"))
      (node (ref "ATSAM4LS") (pin "5") (pinfunction "VDDCORE_5") (pintype "bidirectional"))
      (node (ref "ATSAM4LS") (pin "7") (pinfunction "VDDOUT_7") (pintype "bidirectional"))
      (node (ref "ATSAM4LS") (pin "8") (pinfunction "VDDIN_8") (pintype "bidirectional"))
      (node (ref "C1") (pin "1") (pinfunction "1_1") (pintype "passive"))
      (node (ref "C18") (pin "1") (pinfunction "1_1") (pintype "passive"))
      (node (ref "C19") (pin "1") (pinfunction "1_1") (pintype "passive"))
      (node (ref "C20") (pin "1") (pinfunction "1_1") (pintype "passive"))
      (node (ref "C21") (pin "1") (pinfunction "1_1") (pintype "passive"))
      (node (ref "JTAG") (pin "1") (pinfunction "1_1") (pintype "passive"))
      (node (ref "R1") (pin "1") (pinfunction "1_1") (pintype "passive"))
      (node (ref "R14") (pin "1") (pinfunction "1_1") (pintype "passive"))
      (node (ref "R15") (pin "1") (pinfunction "1_1") (pintype "passive"))
      (node (ref "R16") (pin "1") (pinfunction "1_1") (pintype "passive"))
      (node (ref "R2") (pin "1") (pinfunction "1_1") (pintype "passive"))
      (node (ref "R3") (pin "1") (pinfunction "1_1") (pintype "passive"))
      (node (ref "R5") (pin "2") (pinfunction "2_2") (pintype "passive"))
      (node (ref "R8") (pin "2") (pinfunction "2_2") (pintype "passive"))
      (node (ref "SV3") (pin "10") (pinfunction "10_10") (pintype "passive"))
      (node (ref "SV3") (pin "8") (pinfunction "8_8") (pintype "passive"))
      (node (ref "SV4") (pin "1") (pinfunction "1_1") (pintype "passive"))
      (node (ref "SV4") (pin "3") (pinfunction "3_3") (pintype "passive"))
      (node (ref "U$1") (pin "8") (pinfunction "V+_8") (pintype "power_in"))
      (node (ref "U$4") (pin "8") (pinfunction "V+_8") (pintype "power_in"))
      (node (ref "U$6") (pin "3") (pinfunction "A_3") (pintype "passive"))
      (node (ref "U$7") (pin "2") (pinfunction "OUT_2") (pintype "output"))
      (node (ref "U1") (pin "14") (pinfunction "VCC_14") (pintype "bidirectional"))
    )
    (net (code "62") (name "unconnected-(ATSAM4LS-PA07-Pad16)") (class "Default")
      (node (ref "ATSAM4LS") (pin "16") (pinfunction "PA07_16") (pintype "bidirectional"))
    )
    (net (code "63") (name "unconnected-(ATSAM4LS-PA10-Pad22)") (class "Default")
      (node (ref "ATSAM4LS") (pin "22") (pinfunction "PA10_22") (pintype "bidirectional"))
    )
    (net (code "64") (name "unconnected-(ATSAM4LS-PA13-Pad32)") (class "Default")
      (node (ref "ATSAM4LS") (pin "32") (pinfunction "PA13_32") (pintype "bidirectional"))
    )
    (net (code "65") (name "unconnected-(ATSAM4LS-PA14-Pad33)") (class "Default")
      (node (ref "ATSAM4LS") (pin "33") (pinfunction "PA14_33") (pintype "bidirectional"))
    )
    (net (code "66") (name "unconnected-(ATSAM4LS-PA15-Pad34)") (class "Default")
      (node (ref "ATSAM4LS") (pin "34") (pinfunction "PA15_34") (pintype "bidirectional"))
    )
    (net (code "67") (name "unconnected-(ATSAM4LS-PA16-Pad35)") (class "Default")
      (node (ref "ATSAM4LS") (pin "35") (pinfunction "PA16_35") (pintype "bidirectional"))
    )
    (net (code "68") (name "unconnected-(ATSAM4LS-PA18-Pad37)") (class "Default")
      (node (ref "ATSAM4LS") (pin "37") (pinfunction "PA18_37") (pintype "bidirectional"))
    )
    (net (code "69") (name "unconnected-(ATSAM4LS-PA30-Pad30)") (class "Default")
      (node (ref "ATSAM4LS") (pin "30") (pinfunction "PA30_30") (pintype "bidirectional"))
    )
    (net (code "70") (name "unconnected-(ATSAM4LS-PA31-Pad31)") (class "Default")
      (node (ref "ATSAM4LS") (pin "31") (pinfunction "PA31_31") (pintype "bidirectional"))
    )
    (net (code "71") (name "unconnected-(H1-MOUNT-PadB3,0)") (class "Default")
      (node (ref "H1") (pin "B3,0") (pinfunction "MOUNT_B3,0") (pintype "passive"))
    )
    (net (code "72") (name "unconnected-(H2-MOUNT-PadB3,0)") (class "Default")
      (node (ref "H2") (pin "B3,0") (pinfunction "MOUNT_B3,0") (pintype "passive"))
    )
    (net (code "73") (name "unconnected-(H3-MOUNT-PadB3,0)") (class "Default")
      (node (ref "H3") (pin "B3,0") (pinfunction "MOUNT_B3,0") (pintype "passive"))
    )
    (net (code "74") (name "unconnected-(H4-MOUNT-PadB3,0)") (class "Default")
      (node (ref "H4") (pin "B3,0") (pinfunction "MOUNT_B3,0") (pintype "passive"))
    )
    (net (code "75") (name "unconnected-(JTAG-Pad7)") (class "Default")
      (node (ref "JTAG") (pin "7") (pinfunction "7_7") (pintype "passive"))
    )
  )
)
